# A3988_Breakout.net
KiCad netlist of a schematic drawn in Altium Designer
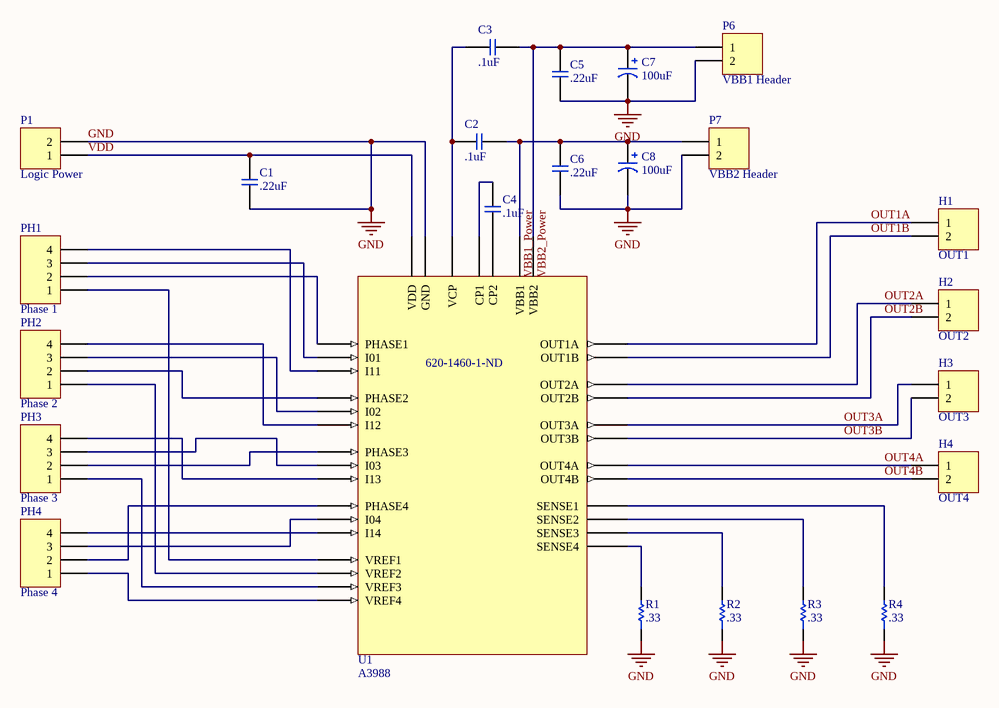
[diagram p0: A3988 Breakout.SchDoc]

(export (version "E")
  (design (tool "Eeschema 10.0.6"))
  (components
    (comp (ref "C1")
      (value ".22uF")
      (footprint "C0805N")
      (libsource (lib "Passive Components") (part "Capacitor"))
    )
    (comp (ref "C2")
      (value ".1uF")
      (footprint "C0805N")
      (libsource (lib "Passive Components") (part "Capacitor"))
    )
    (comp (ref "C3")
      (value ".1uF")
      (footprint "C0805N")
      (libsource (lib "Passive Components") (part "Capacitor"))
    )
    (comp (ref "C4")
      (value ".1uF")
      (footprint "C0805N")
      (libsource (lib "Passive Components") (part "Capacitor"))
    )
    (comp (ref "C5")
      (value ".22uF")
      (footprint "C0805N")
      (libsource (lib "Passive Components") (part "Capacitor"))
    )
    (comp (ref "C6")
      (value ".22uF")
      (footprint "C0805N")
      (libsource (lib "Passive Components") (part "Capacitor"))
    )
    (comp (ref "C7")
      (value "100uF")
      (footprint "F")
      (libsource (lib "Passive Components") (part "Electrolytic Capacitor"))
    )
    (comp (ref "C8")
      (value "100uF")
      (footprint "F")
      (libsource (lib "Passive Components") (part "Electrolytic Capacitor"))
    )
    (comp (ref "H1")
      (value "OUT1")
      (footprint "HDR1X2")
      (description "Header, 2-Pin")
      (fields (field (name "PUBLISHER") "Altium Limited"))
      (libsource (lib "Miscellaneous Connectors") (part "Header 2"))
    )
    (comp (ref "H2")
      (value "OUT2")
      (footprint "HDR1X2")
      (description "Header, 2-Pin")
      (fields (field (name "PUBLISHER") "Altium Limited"))
      (libsource (lib "Miscellaneous Connectors") (part "Header 2"))
    )
    (comp (ref "H3")
      (value "OUT3")
      (footprint "HDR1X2")
      (description "Header, 2-Pin")
      (fields (field (name "PUBLISHER") "Altium Limited"))
      (libsource (lib "Miscellaneous Connectors") (part "Header 2"))
    )
    (comp (ref "H4")
      (value "OUT4")
      (footprint "HDR1X2")
      (description "Header, 2-Pin")
      (fields (field (name "PUBLISHER") "Altium Limited"))
      (libsource (lib "Miscellaneous Connectors") (part "Header 2"))
    )
    (comp (ref "P1")
      (value "Logic Power")
      (footprint "HDR1X2")
      (description "Header, 2-Pin")
      (fields (field (name "PUBLISHER") "Altium Limited"))
      (libsource (lib "") (part "Header 2_1"))
    )
    (comp (ref "P6")
      (value "VBB1 Header")
      (footprint "HDR1X2")
      (description "Header, 2-Pin")
      (fields (field (name "PUBLISHER") "Altium Limited"))
      (libsource (lib "Miscellaneous Connectors") (part "Header 2"))
    )
    (comp (ref "P7")
      (value "VBB2 Header")
      (footprint "HDR1X2")
      (description "Header, 2-Pin")
      (fields (field (name "PUBLISHER") "Altium Limited"))
      (libsource (lib "Miscellaneous Connectors") (part "Header 2"))
    )
    (comp (ref "PH1")
      (value "Phase 1")
      (footprint "HDR1X4")
      (description "Header, 4-Pin")
      (fields (field (name "PUBLISHER") "Altium Limited"))
      (libsource (lib "Miscellaneous Connectors") (part "Header 4"))
    )
    (comp (ref "PH2")
      (value "Phase 2")
      (footprint "HDR1X4")
      (description "Header, 4-Pin")
      (fields (field (name "PUBLISHER") "Altium Limited"))
      (libsource (lib "Miscellaneous Connectors") (part "Header 4"))
    )
    (comp (ref "PH3")
      (value "Phase 3")
      (footprint "HDR1X4")
      (description "Header, 4-Pin")
      (fields (field (name "PUBLISHER") "Altium Limited"))
      (libsource (lib "Miscellaneous Connectors") (part "Header 4"))
    )
    (comp (ref "PH4")
      (value "Phase 4")
      (footprint "HDR1X4")
      (description "Header, 4-Pin")
      (fields (field (name "PUBLISHER") "Altium Limited"))
      (libsource (lib "Miscellaneous Connectors") (part "Header 4"))
    )
    (comp (ref "R1")
      (value ".33")
      (footprint "R2512N")
      (description "Passive Resistor")
      (libsource (lib "Passive Components") (part "Resistor"))
    )
    (comp (ref "R2")
      (value ".33")
      (footprint "R2512N")
      (description "Passive Resistor")
      (libsource (lib "Passive Components") (part "Resistor"))
    )
    (comp (ref "R3")
      (value ".33")
      (footprint "R2512N")
      (description "Passive Resistor")
      (libsource (lib "Passive Components") (part "Resistor"))
    )
    (comp (ref "R4")
      (value ".33")
      (footprint "R2512N")
      (description "Passive Resistor")
      (libsource (lib "Passive Components") (part "Resistor"))
    )
    (comp (ref "U1")
      (value "A3988")
      (footprint "JP")
      (description "Quad DMOS Full Bridge PWM Motor Driver")
      (fields (field (name "SUPPLIER PART NUMBER 1") "620-1460-1-ND"))
      (libsource (lib "Allegro - Motor Driver ICs") (part "A3988"))
    )
  )
  (nets
    (net (code "1") (name "/OUT1A") (class "Default")
      (node (ref "H1") (pin "1") (pinfunction "1_1") (pintype "passive"))
      (node (ref "U1") (pin "OUT1A") (pinfunction "OUT1A_OUT1A") (pintype "output"))
    )
    (net (code "2") (name "/OUT1B") (class "Default")
      (node (ref "H1") (pin "2") (pinfunction "2_2") (pintype "passive"))
      (node (ref "U1") (pin "OUT1B") (pinfunction "OUT1B_OUT1B") (pintype "output"))
    )
    (net (code "3") (name "/OUT2A") (class "Default")
      (node (ref "H2") (pin "1") (pinfunction "1_1") (pintype "passive"))
      (node (ref "U1") (pin "OUT2A") (pinfunction "OUT2A_OUT2A") (pintype "output"))
    )
    (net (code "4") (name "/OUT2B") (class "Default")
      (node (ref "H2") (pin "2") (pinfunction "2_2") (pintype "passive"))
      (node (ref "U1") (pin "OUT2B") (pinfunction "OUT2B_OUT2B") (pintype "output"))
    )
    (net (code "5") (name "/OUT3A") (class "Default")
      (node (ref "H3") (pin "1") (pinfunction "1_1") (pintype "passive"))
      (node (ref "U1") (pin "OUT3A") (pinfunction "OUT3A_OUT3A") (pintype "output"))
    )
    (net (code "6") (name "/OUT3B") (class "Default")
      (node (ref "H3") (pin "2") (pinfunction "2_2") (pintype "passive"))
      (node (ref "U1") (pin "OUT3B") (pinfunction "OUT3B_OUT3B") (pintype "output"))
    )
    (net (code "7") (name "/OUT4A") (class "Default")
      (node (ref "H4") (pin "1") (pinfunction "1_1") (pintype "passive"))
      (node (ref "U1") (pin "OUT4A") (pinfunction "OUT4A_OUT4A") (pintype "output"))
    )
    (net (code "8") (name "/OUT4B") (class "Default")
      (node (ref "H4") (pin "2") (pinfunction "2_2") (pintype "passive"))
      (node (ref "U1") (pin "OUT4B") (pinfunction "OUT4B_OUT4B") (pintype "output"))
    )
    (net (code "9") (name "/VBB1_Power") (class "Default")
      (node (ref "C2") (pin "1") (pinfunction "1_1") (pintype "passive"))
      (node (ref "C6") (pin "2") (pinfunction "2_2") (pintype "passive"))
      (node (ref "C8") (pin "1") (pinfunction "1_1") (pintype "passive"))
      (node (ref "P7") (pin "1") (pinfunction "1_1") (pintype "passive"))
      (node (ref "U1") (pin "VBB1") (pinfunction "VBB1_VBB1") (pintype "power_in"))
    )
    (net (code "10") (name "/VBB2_Power") (class "Default")
      (node (ref "C3") (pin "1") (pinfunction "1_1") (pintype "passive"))
      (node (ref "C5") (pin "2") (pinfunction "2_2") (pintype "passive"))
      (node (ref "C7") (pin "1") (pinfunction "1_1") (pintype "passive"))
      (node (ref "P6") (pin "1") (pinfunction "1_1") (pintype "passive"))
      (node (ref "U1") (pin "VBB2") (pinfunction "VBB2_VBB2") (pintype "power_in"))
    )
    (net (code "11") (name "/VDD") (class "Default")
      (node (ref "C1") (pin "2") (pinfunction "2_2") (pintype "passive"))
      (node (ref "P1") (pin "1") (pinfunction "1_1") (pintype "passive"))
      (node (ref "U1") (pin "VDD") (pinfunction "VDD_VDD") (pintype "power_in"))
    )
    (net (code "12") (name "GND") (class "Default")
      (node (ref "C1") (pin "1") (pinfunction "1_1") (pintype "passive"))
      (node (ref "C5") (pin "1") (pinfunction "1_1") (pintype "passive"))
      (node (ref "C6") (pin "1") (pinfunction "1_1") (pintype "passive"))
      (node (ref "C7") (pin "2") (pinfunction "2_2") (pintype "passive"))
      (node (ref "C8") (pin "2") (pinfunction "2_2") (pintype "passive"))
      (node (ref "P1") (pin "2") (pinfunction "2_2") (pintype "passive"))
      (node (ref "P6") (pin "2") (pinfunction "2_2") (pintype "passive"))
      (node (ref "P7") (pin "2") (pinfunction "2_2") (pintype "passive"))
      (node (ref "R1") (pin "2") (pinfunction "2_2") (pintype "passive"))
      (node (ref "R2") (pin "2") (pinfunction "2_2") (pintype "passive"))
      (node (ref "R3") (pin "2") (pinfunction "2_2") (pintype "passive"))
      (node (ref "R4") (pin "2") (pinfunction "2_2") (pintype "passive"))
      (node (ref "U1") (pin "GND") (pinfunction "GND_GND") (pintype "power_in"))
    )
    (net (code "13") (name "Net-(C2-Pad2)") (class "Default")
      (node (ref "C2") (pin "2") (pinfunction "2_2") (pintype "passive"))
      (node (ref "C3") (pin "2") (pinfunction "2_2") (pintype "passive"))
      (node (ref "U1") (pin "VCP") (pinfunction "VCP_VCP") (pintype "passive"))
    )
    (net (code "14") (name "Net-(C4-Pad1)") (class "Default")
      (node (ref "C4") (pin "1") (pinfunction "1_1") (pintype "passive"))
      (node (ref "U1") (pin "CP2") (pinfunction "CP2_CP2") (pintype "passive"))
    )
    (net (code "15") (name "Net-(C4-Pad2)") (class "Default")
      (node (ref "C4") (pin "2") (pinfunction "2_2") (pintype "passive"))
      (node (ref "U1") (pin "CP1") (pinfunction "CP1_CP1") (pintype "passive"))
    )
    (net (code "16") (name "Net-(PH1-Pad1)") (class "Default")
      (node (ref "PH1") (pin "1") (pinfunction "1_1") (pintype "passive"))
      (node (ref "U1") (pin "VREF1") (pinfunction "VREF1_VREF1") (pintype "input"))
    )
    (net (code "17") (name "Net-(PH1-Pad2)") (class "Default")
      (node (ref "PH1") (pin "2") (pinfunction "2_2") (pintype "passive"))
      (node (ref "U1") (pin "PHASE1") (pinfunction "PHASE1_PHASE1") (pintype "input"))
    )
    (net (code "18") (name "Net-(PH1-Pad3)") (class "Default")
      (node (ref "PH1") (pin "3") (pinfunction "3_3") (pintype "passive"))
      (node (ref "U1") (pin "I01") (pinfunction "I01_I01") (pintype "input"))
    )
    (net (code "19") (name "Net-(PH1-Pad4)") (class "Default")
      (node (ref "PH1") (pin "4") (pinfunction "4_4") (pintype "passive"))
      (node (ref "U1") (pin "I11") (pinfunction "I11_I11") (pintype "input"))
    )
    (net (code "20") (name "Net-(PH2-Pad1)") (class "Default")
      (node (ref "PH2") (pin "1") (pinfunction "1_1") (pintype "passive"))
      (node (ref "U1") (pin "VREF2") (pinfunction "VREF2_VREF2") (pintype "input"))
    )
    (net (code "21") (name "Net-(PH2-Pad2)") (class "Default")
      (node (ref "PH2") (pin "2") (pinfunction "2_2") (pintype "passive"))
      (node (ref "U1") (pin "PHASE2") (pinfunction "PHASE2_PHASE2") (pintype "input"))
    )
    (net (code "22") (name "Net-(PH2-Pad3)") (class "Default")
      (node (ref "PH2") (pin "3") (pinfunction "3_3") (pintype "passive"))
      (node (ref "U1") (pin "I02") (pinfunction "I02_I02") (pintype "input"))
    )
    (net (code "23") (name "Net-(PH2-Pad4)") (class "Default")
      (node (ref "PH2") (pin "4") (pinfunction "4_4") (pintype "passive"))
      (node (ref "U1") (pin "I12") (pinfunction "I12_I12") (pintype "input"))
    )
    (net (code "24") (name "Net-(PH3-Pad1)") (class "Default")
      (node (ref "PH3") (pin "1") (pinfunction "1_1") (pintype "passive"))
      (node (ref "U1") (pin "VREF3") (pinfunction "VREF3_VREF3") (pintype "input"))
    )
    (net (code "25") (name "Net-(PH3-Pad2)") (class "Default")
      (node (ref "PH3") (pin "2") (pinfunction "2_2") (pintype "passive"))
      (node (ref "U1") (pin "PHASE3") (pinfunction "PHASE3_PHASE3") (pintype "input"))
    )
    (net (code "26") (name "Net-(PH3-Pad3)") (class "Default")
      (node (ref "PH3") (pin "3") (pinfunction "3_3") (pintype "passive"))
      (node (ref "U1") (pin "I03") (pinfunction "I03_I03") (pintype "input"))
    )
    (net (code "27") (name "Net-(PH3-Pad4)") (class "Default")
      (node (ref "PH3") (pin "4") (pinfunction "4_4") (pintype "passive"))
      (node (ref "U1") (pin "I13") (pinfunction "I13_I13") (pintype "input"))
    )
    (net (code "28") (name "Net-(PH4-Pad1)") (class "Default")
      (node (ref "PH4") (pin "1") (pinfunction "1_1") (pintype "passive"))
      (node (ref "U1") (pin "VREF4") (pinfunction "VREF4_VREF4") (pintype "input"))
    )
    (net (code "29") (name "Net-(PH4-Pad2)") (class "Default")
      (node (ref "PH4") (pin "2") (pinfunction "2_2") (pintype "passive"))
      (node (ref "U1") (pin "PHASE4") (pinfunction "PHASE4_PHASE4") (pintype "input"))
    )
    (net (code "30") (name "Net-(PH4-Pad3)") (class "Default")
      (node (ref "PH4") (pin "3") (pinfunction "3_3") (pintype "passive"))
      (node (ref "U1") (pin "I04") (pinfunction "I04_I04") (pintype "input"))
    )
    (net (code "31") (name "Net-(PH4-Pad4)") (class "Default")
      (node (ref "PH4") (pin "4") (pinfunction "4_4") (pintype "passive"))
      (node (ref "U1") (pin "I14") (pinfunction "I14_I14") (pintype "input"))
    )
    (net (code "32") (name "Net-(R1-Pad1)") (class "Default")
      (node (ref "R1") (pin "1") (pinfunction "1_1") (pintype "passive"))
      (node (ref "U1") (pin "SENSE4") (pinfunction "SENSE4_SENSE4") (pintype "passive"))
    )
    (net (code "33") (name "Net-(R2-Pad1)") (class "Default")
      (node (ref "R2") (pin "1") (pinfunction "1_1") (pintype "passive"))
      (node (ref "U1") (pin "SENSE3") (pinfunction "SENSE3_SENSE3") (pintype "passive"))
    )
    (net (code "34") (name "Net-(R3-Pad1)") (class "Default")
      (node (ref "R3") (pin "1") (pinfunction "1_1") (pintype "passive"))
      (node (ref "U1") (pin "SENSE2") (pinfunction "SENSE2_SENSE2") (pintype "passive"))
    )
    (net (code "35") (name "Net-(R4-Pad1)") (class "Default")
      (node (ref "R4") (pin "1") (pinfunction "1_1") (pintype "passive"))
      (node (ref "U1") (pin "SENSE1") (pinfunction "SENSE1_SENSE1") (pintype "passive"))
    )
  )
)
